# led_board_robot_vs_v2_final.net
KiCad netlist of a schematic drawn in EAGLE
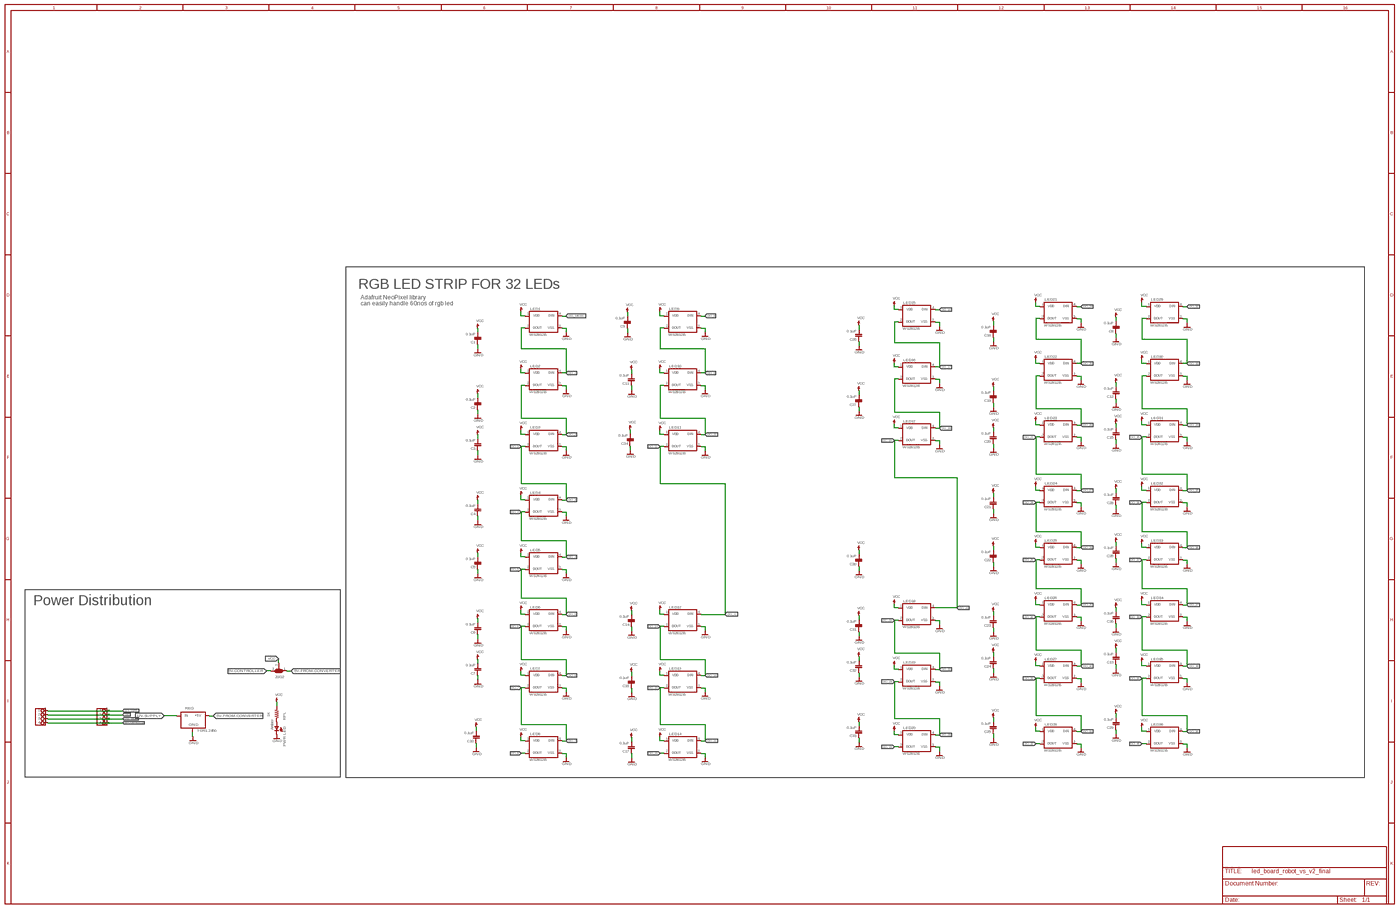
[diagram p0: schematic, sheet 1, overview]
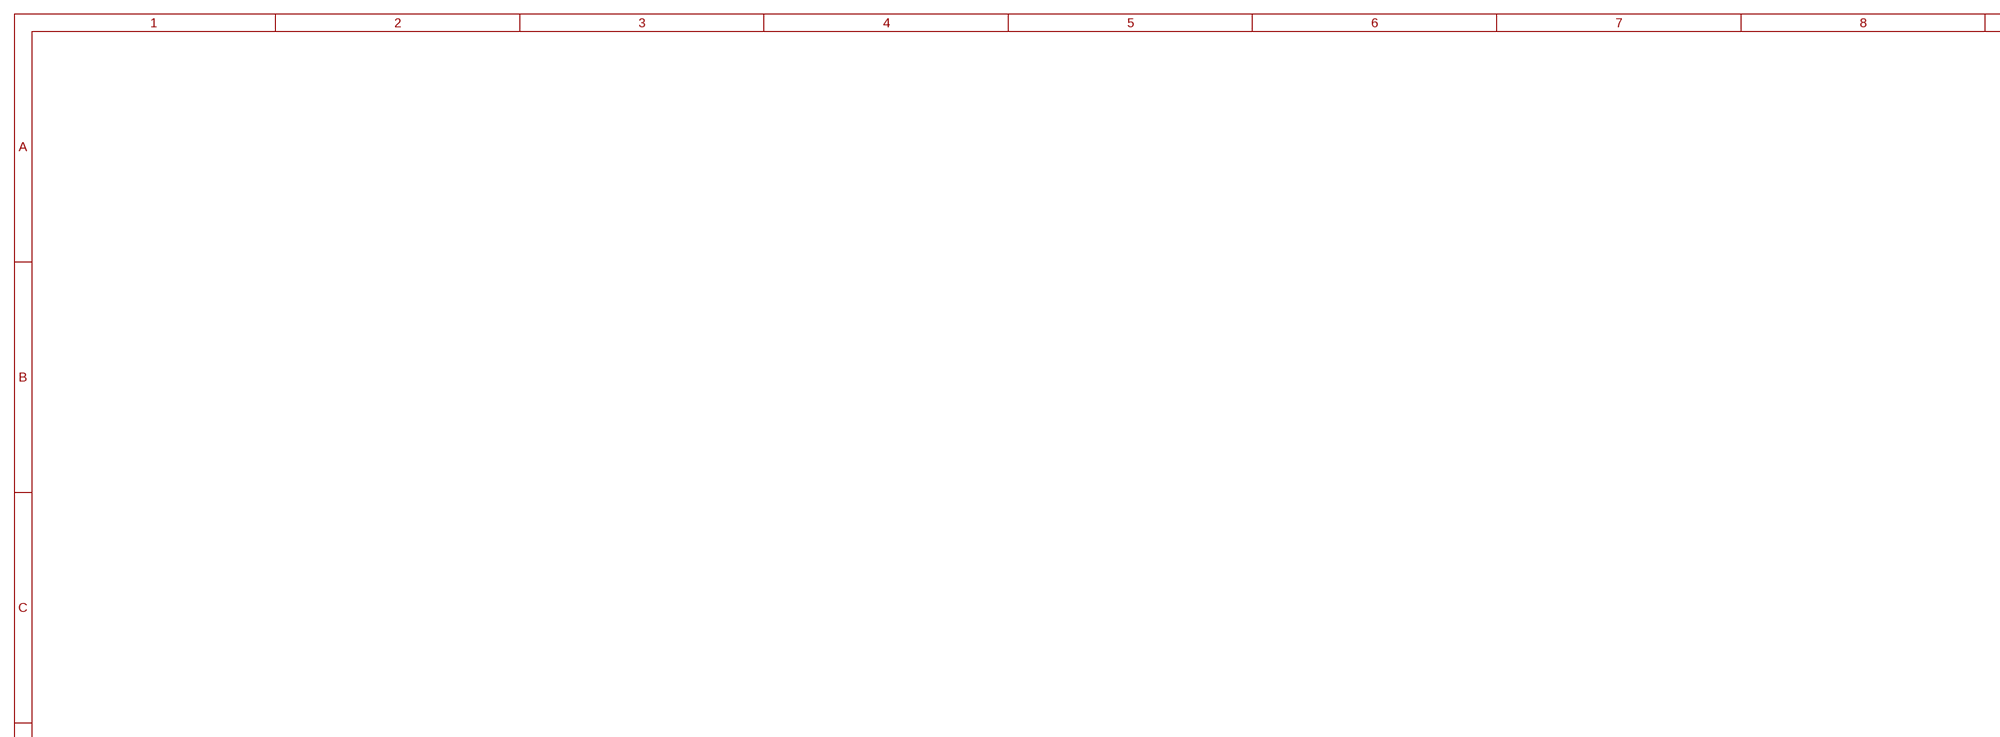
[diagram p1: schematic, sheet 1, part 1 of 4]
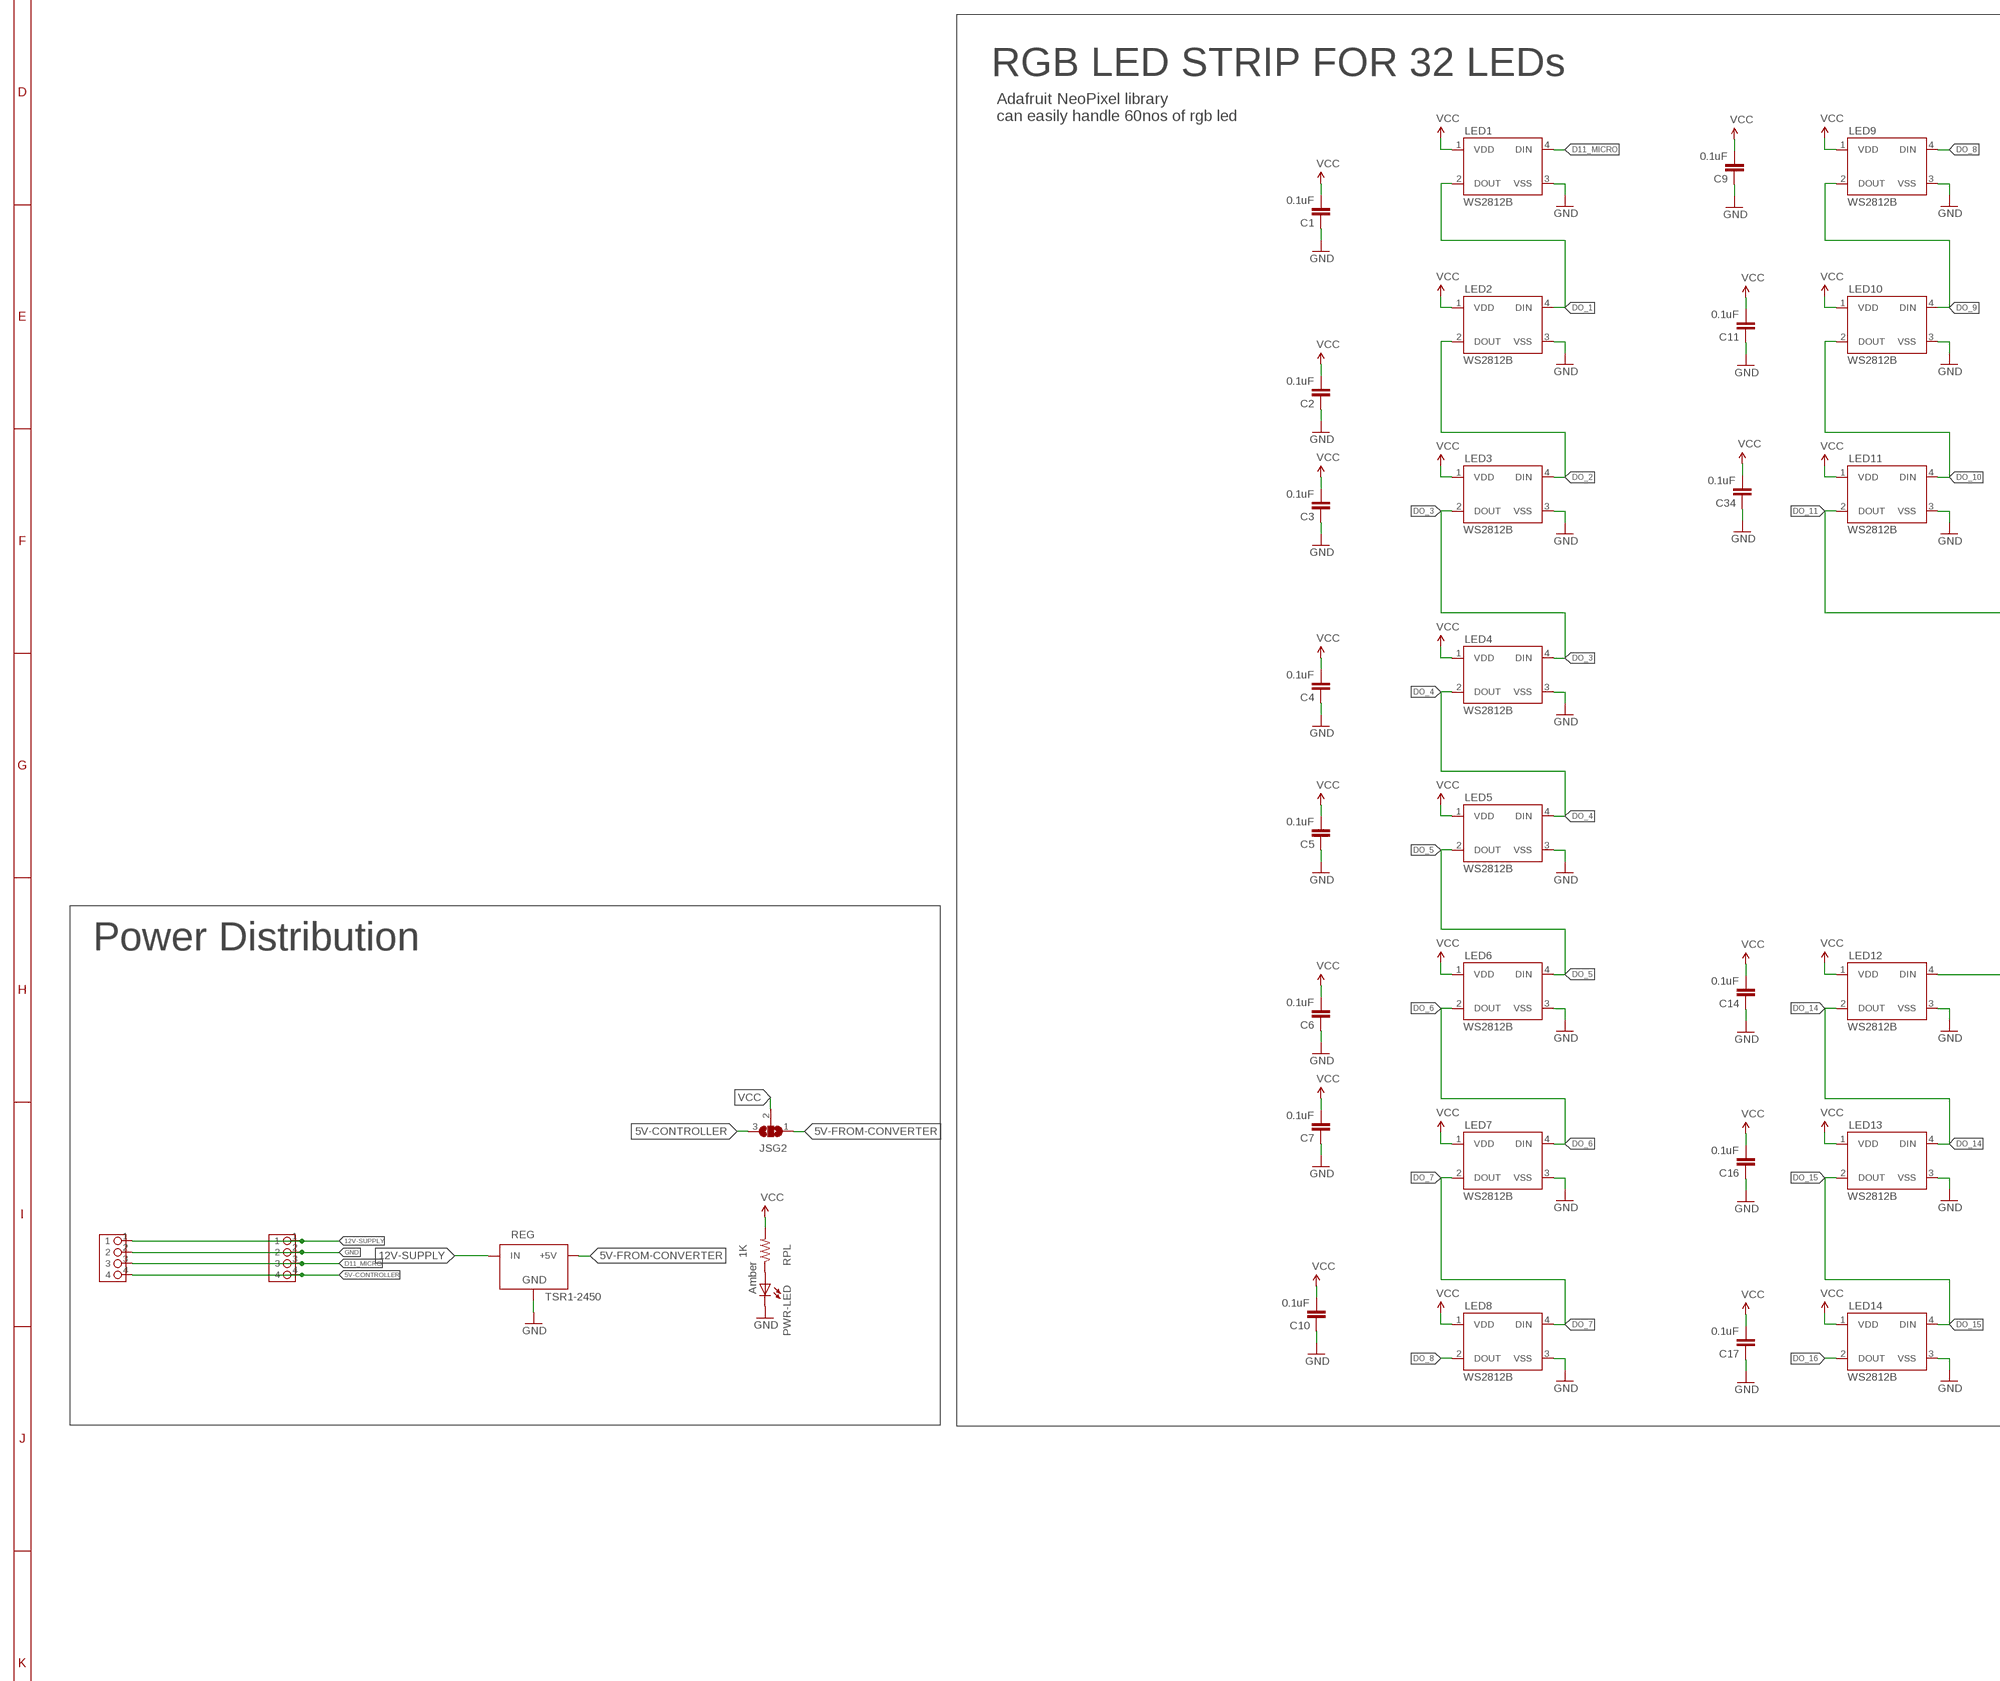
[diagram p2: schematic, sheet 1, part 2 of 4]
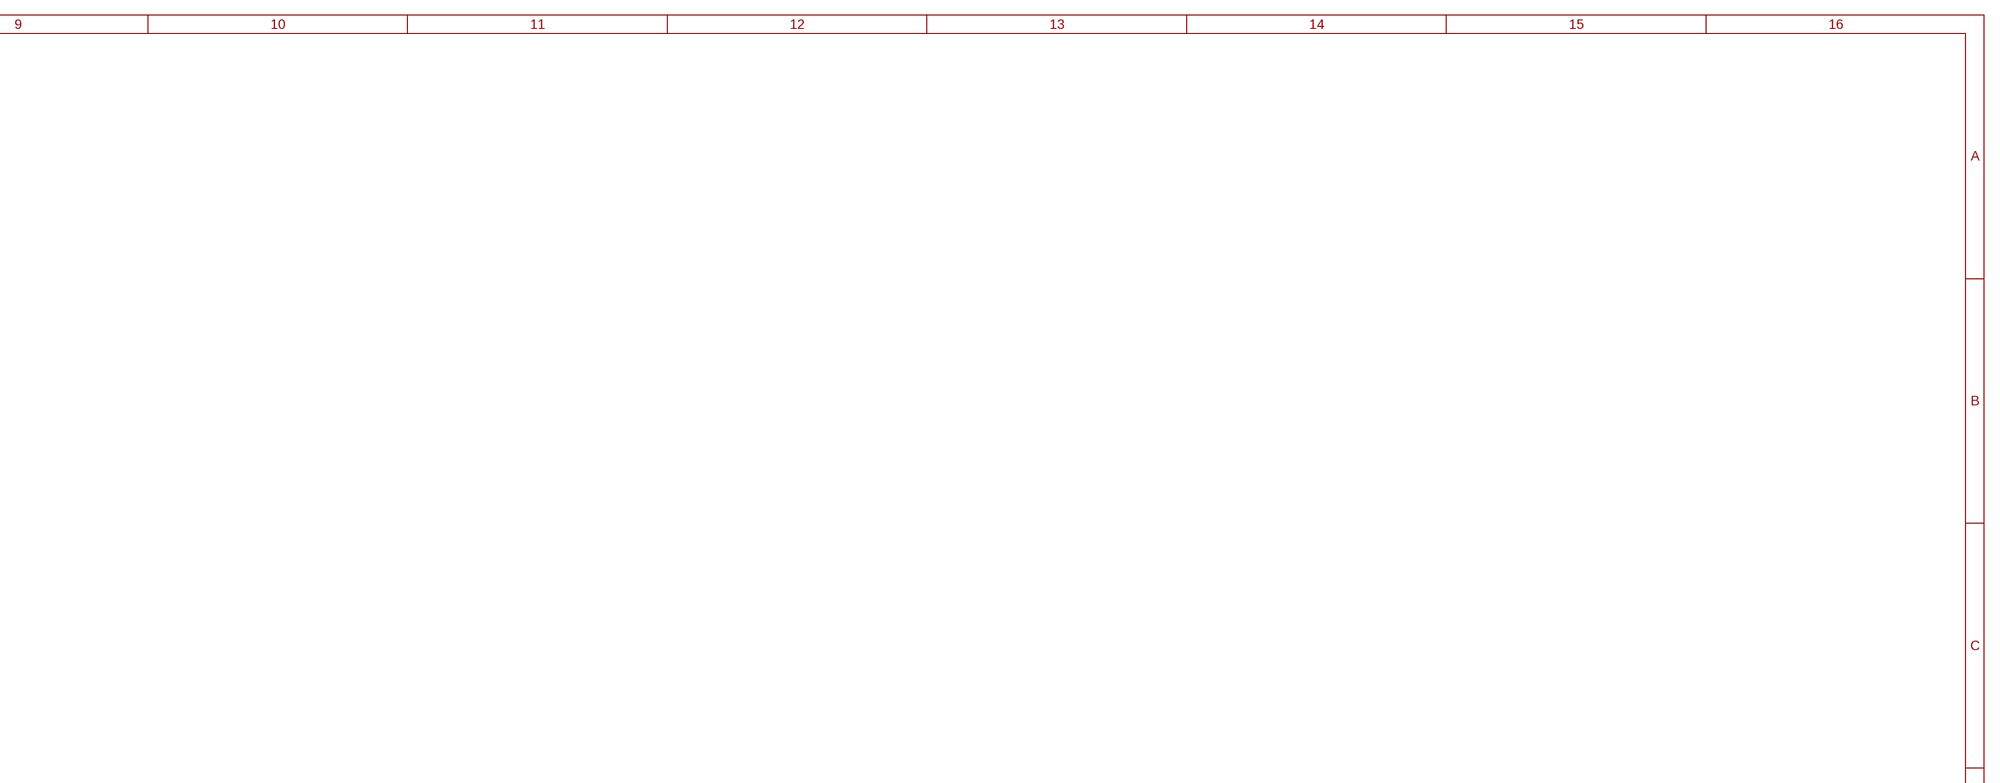
[diagram p3: schematic, sheet 1, part 3 of 4]
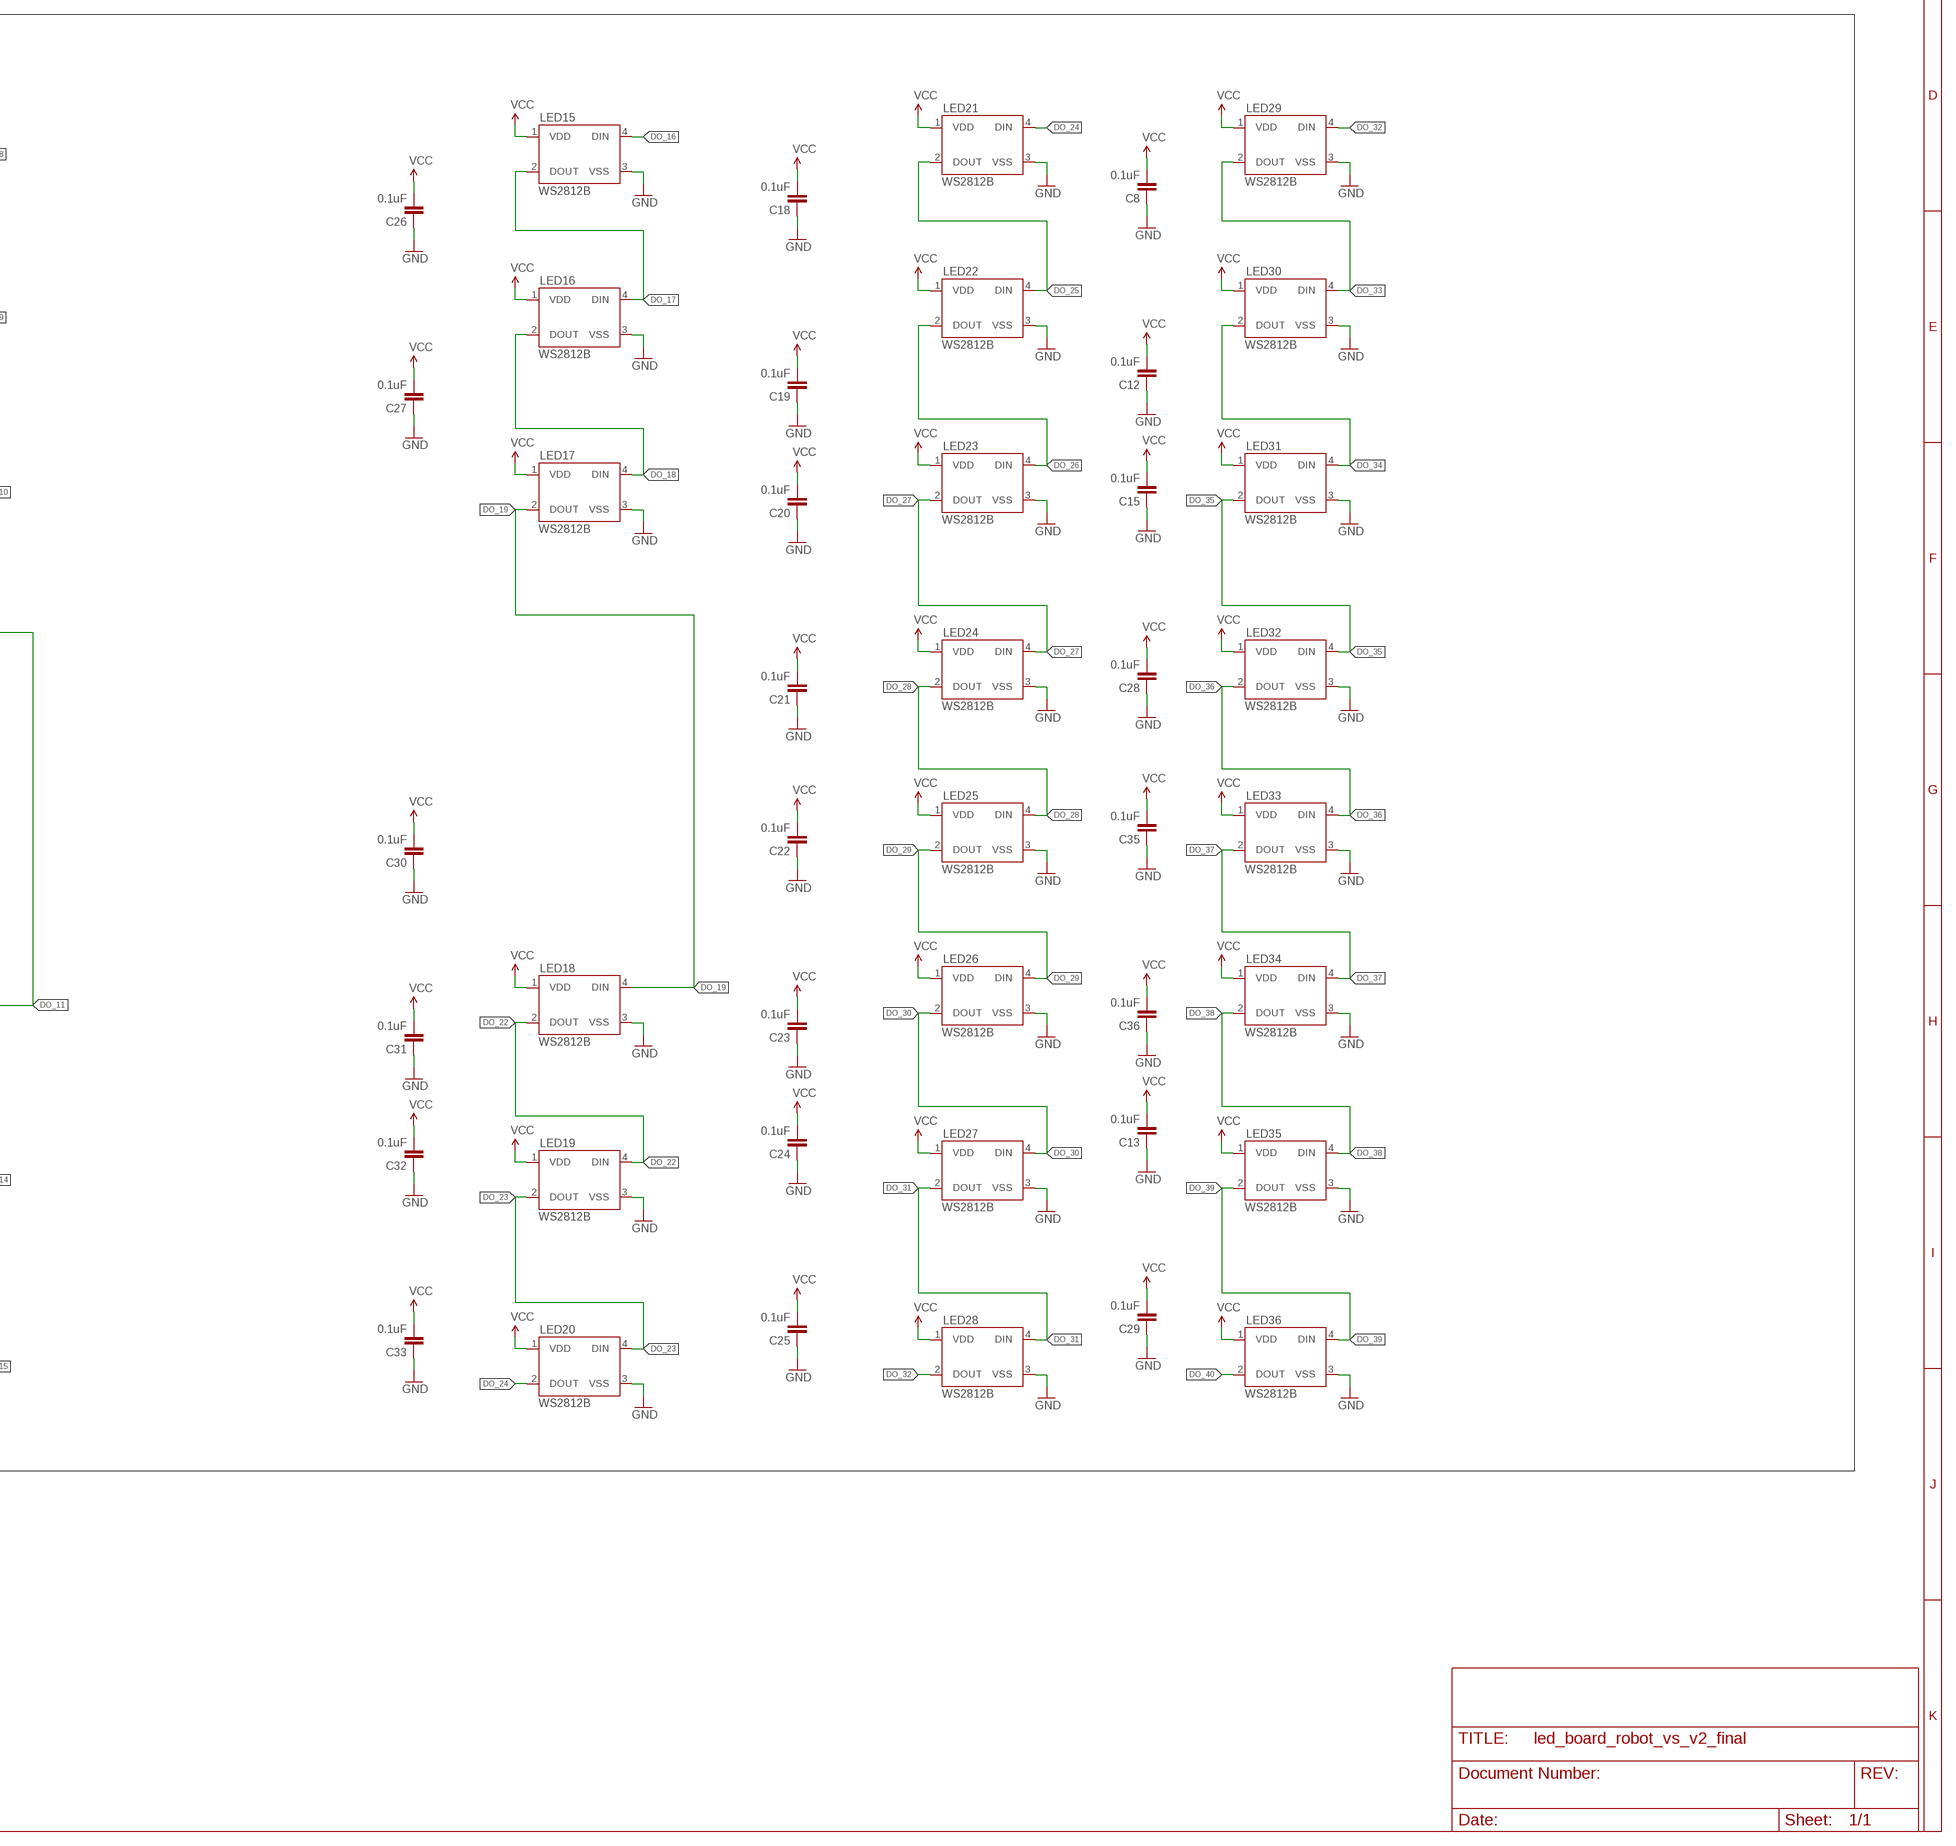
[diagram p4: schematic, sheet 1, part 4 of 4]

(export (version "E")
  (design (tool "Eeschema 10.0.6"))
  (components
    (comp (ref "C1")
      (value "0.1uF")
      (footprint "eagle-import:0603-CAP")
      (libsource (lib "eagle-import") (part "CAP0603-CAP"))
    )
    (comp (ref "C2")
      (value "0.1uF")
      (footprint "eagle-import:0603-CAP")
      (libsource (lib "eagle-import") (part "CAP0603-CAP"))
    )
    (comp (ref "C3")
      (value "0.1uF")
      (footprint "eagle-import:0603-CAP")
      (libsource (lib "eagle-import") (part "CAP0603-CAP"))
    )
    (comp (ref "C4")
      (value "0.1uF")
      (footprint "eagle-import:0603-CAP")
      (libsource (lib "eagle-import") (part "CAP0603-CAP"))
    )
    (comp (ref "C5")
      (value "0.1uF")
      (footprint "eagle-import:0603-CAP")
      (libsource (lib "eagle-import") (part "CAP0603-CAP"))
    )
    (comp (ref "C6")
      (value "0.1uF")
      (footprint "eagle-import:0603-CAP")
      (libsource (lib "eagle-import") (part "CAP0603-CAP"))
    )
    (comp (ref "C7")
      (value "0.1uF")
      (footprint "eagle-import:0603-CAP")
      (libsource (lib "eagle-import") (part "CAP0603-CAP"))
    )
    (comp (ref "C8")
      (value "0.1uF")
      (footprint "eagle-import:0603-CAP")
      (libsource (lib "eagle-import") (part "CAP0603-CAP"))
    )
    (comp (ref "C9")
      (value "0.1uF")
      (footprint "eagle-import:0603-CAP")
      (libsource (lib "eagle-import") (part "CAP0603-CAP"))
    )
    (comp (ref "C10")
      (value "0.1uF")
      (footprint "eagle-import:0603-CAP")
      (libsource (lib "eagle-import") (part "CAP0603-CAP"))
    )
    (comp (ref "C11")
      (value "0.1uF")
      (footprint "eagle-import:0603-CAP")
      (libsource (lib "eagle-import") (part "CAP0603-CAP"))
    )
    (comp (ref "C12")
      (value "0.1uF")
      (footprint "eagle-import:0603-CAP")
      (libsource (lib "eagle-import") (part "CAP0603-CAP"))
    )
    (comp (ref "C13")
      (value "0.1uF")
      (footprint "eagle-import:0603-CAP")
      (libsource (lib "eagle-import") (part "CAP0603-CAP"))
    )
    (comp (ref "C14")
      (value "0.1uF")
      (footprint "eagle-import:0603-CAP")
      (libsource (lib "eagle-import") (part "CAP0603-CAP"))
    )
    (comp (ref "C15")
      (value "0.1uF")
      (footprint "eagle-import:0603-CAP")
      (libsource (lib "eagle-import") (part "CAP0603-CAP"))
    )
    (comp (ref "C16")
      (value "0.1uF")
      (footprint "eagle-import:0603-CAP")
      (libsource (lib "eagle-import") (part "CAP0603-CAP"))
    )
    (comp (ref "C17")
      (value "0.1uF")
      (footprint "eagle-import:0603-CAP")
      (libsource (lib "eagle-import") (part "CAP0603-CAP"))
    )
    (comp (ref "C18")
      (value "0.1uF")
      (footprint "eagle-import:0603-CAP")
      (libsource (lib "eagle-import") (part "CAP0603-CAP"))
    )
    (comp (ref "C19")
      (value "0.1uF")
      (footprint "eagle-import:0603-CAP")
      (libsource (lib "eagle-import") (part "CAP0603-CAP"))
    )
    (comp (ref "C20")
      (value "0.1uF")
      (footprint "eagle-import:0603-CAP")
      (libsource (lib "eagle-import") (part "CAP0603-CAP"))
    )
    (comp (ref "C21")
      (value "0.1uF")
      (footprint "eagle-import:0603-CAP")
      (libsource (lib "eagle-import") (part "CAP0603-CAP"))
    )
    (comp (ref "C22")
      (value "0.1uF")
      (footprint "eagle-import:0603-CAP")
      (libsource (lib "eagle-import") (part "CAP0603-CAP"))
    )
    (comp (ref "C23")
      (value "0.1uF")
      (footprint "eagle-import:0603-CAP")
      (libsource (lib "eagle-import") (part "CAP0603-CAP"))
    )
    (comp (ref "C24")
      (value "0.1uF")
      (footprint "eagle-import:0603-CAP")
      (libsource (lib "eagle-import") (part "CAP0603-CAP"))
    )
    (comp (ref "C25")
      (value "0.1uF")
      (footprint "eagle-import:0603-CAP")
      (libsource (lib "eagle-import") (part "CAP0603-CAP"))
    )
    (comp (ref "C26")
      (value "0.1uF")
      (footprint "eagle-import:0603-CAP")
      (libsource (lib "eagle-import") (part "CAP0603-CAP"))
    )
    (comp (ref "C27")
      (value "0.1uF")
      (footprint "eagle-import:0603-CAP")
      (libsource (lib "eagle-import") (part "CAP0603-CAP"))
    )
    (comp (ref "C28")
      (value "0.1uF")
      (footprint "eagle-import:0603-CAP")
      (libsource (lib "eagle-import") (part "CAP0603-CAP"))
    )
    (comp (ref "C29")
      (value "0.1uF")
      (footprint "eagle-import:0603-CAP")
      (libsource (lib "eagle-import") (part "CAP0603-CAP"))
    )
    (comp (ref "C30")
      (value "0.1uF")
      (footprint "eagle-import:0603-CAP")
      (libsource (lib "eagle-import") (part "CAP0603-CAP"))
    )
    (comp (ref "C31")
      (value "0.1uF")
      (footprint "eagle-import:0603-CAP")
      (libsource (lib "eagle-import") (part "CAP0603-CAP"))
    )
    (comp (ref "C32")
      (value "0.1uF")
      (footprint "eagle-import:0603-CAP")
      (libsource (lib "eagle-import") (part "CAP0603-CAP"))
    )
    (comp (ref "C33")
      (value "0.1uF")
      (footprint "eagle-import:0603-CAP")
      (libsource (lib "eagle-import") (part "CAP0603-CAP"))
    )
    (comp (ref "C34")
      (value "0.1uF")
      (footprint "eagle-import:0603-CAP")
      (libsource (lib "eagle-import") (part "CAP0603-CAP"))
    )
    (comp (ref "C35")
      (value "0.1uF")
      (footprint "eagle-import:0603-CAP")
      (libsource (lib "eagle-import") (part "CAP0603-CAP"))
    )
    (comp (ref "C36")
      (value "0.1uF")
      (footprint "eagle-import:0603-CAP")
      (libsource (lib "eagle-import") (part "CAP0603-CAP"))
    )
    (comp (ref "CON1")
      (value "MOLEX_LOCKING_4PIN")
      (footprint "eagle-import:MOLEX_LOCKING_4PIN")
      (fields (field (name "PARTNO") "43650-0415"))
      (libsource (lib "eagle-import") (part "MOLEX_LOCKING_4PIN"))
    )
    (comp (ref "CON2")
      (value "MOLEX_LOCKING_4PIN")
      (footprint "eagle-import:MOLEX_LOCKING_4PIN")
      (fields (field (name "PARTNO") "43650-0415"))
      (libsource (lib "eagle-import") (part "MOLEX_LOCKING_4PIN"))
    )
    (comp (ref "JSG2")
      (value "SJ2WW")
      (footprint "eagle-import:SJ_2W")
      (libsource (lib "eagle-import") (part "SJ2WW"))
    )
    (comp (ref "LED1")
      (value "WS2812B")
      (footprint "eagle-import:WS2812B")
      (libsource (lib "eagle-import") (part "WS2812B"))
    )
    (comp (ref "LED2")
      (value "WS2812B")
      (footprint "eagle-import:WS2812B")
      (libsource (lib "eagle-import") (part "WS2812B"))
    )
    (comp (ref "LED3")
      (value "WS2812B")
      (footprint "eagle-import:WS2812B")
      (libsource (lib "eagle-import") (part "WS2812B"))
    )
    (comp (ref "LED4")
      (value "WS2812B")
      (footprint "eagle-import:WS2812B")
      (libsource (lib "eagle-import") (part "WS2812B"))
    )
    (comp (ref "LED5")
      (value "WS2812B")
      (footprint "eagle-import:WS2812B")
      (libsource (lib "eagle-import") (part "WS2812B"))
    )
    (comp (ref "LED6")
      (value "WS2812B")
      (footprint "eagle-import:WS2812B")
      (libsource (lib "eagle-import") (part "WS2812B"))
    )
    (comp (ref "LED7")
      (value "WS2812B")
      (footprint "eagle-import:WS2812B")
      (libsource (lib "eagle-import") (part "WS2812B"))
    )
    (comp (ref "LED8")
      (value "WS2812B")
      (footprint "eagle-import:WS2812B")
      (libsource (lib "eagle-import") (part "WS2812B"))
    )
    (comp (ref "LED9")
      (value "WS2812B")
      (footprint "eagle-import:WS2812B")
      (libsource (lib "eagle-import") (part "WS2812B"))
    )
    (comp (ref "LED10")
      (value "WS2812B")
      (footprint "eagle-import:WS2812B")
      (libsource (lib "eagle-import") (part "WS2812B"))
    )
    (comp (ref "LED11")
      (value "WS2812B")
      (footprint "eagle-import:WS2812B")
      (libsource (lib "eagle-import") (part "WS2812B"))
    )
    (comp (ref "LED12")
      (value "WS2812B")
      (footprint "eagle-import:WS2812B")
      (libsource (lib "eagle-import") (part "WS2812B"))
    )
    (comp (ref "LED13")
      (value "WS2812B")
      (footprint "eagle-import:WS2812B")
      (libsource (lib "eagle-import") (part "WS2812B"))
    )
    (comp (ref "LED14")
      (value "WS2812B")
      (footprint "eagle-import:WS2812B")
      (libsource (lib "eagle-import") (part "WS2812B"))
    )
    (comp (ref "LED15")
      (value "WS2812B")
      (footprint "eagle-import:WS2812B")
      (libsource (lib "eagle-import") (part "WS2812B"))
    )
    (comp (ref "LED16")
      (value "WS2812B")
      (footprint "eagle-import:WS2812B")
      (libsource (lib "eagle-import") (part "WS2812B"))
    )
    (comp (ref "LED17")
      (value "WS2812B")
      (footprint "eagle-import:WS2812B")
      (libsource (lib "eagle-import") (part "WS2812B"))
    )
    (comp (ref "LED18")
      (value "WS2812B")
      (footprint "eagle-import:WS2812B")
      (libsource (lib "eagle-import") (part "WS2812B"))
    )
    (comp (ref "LED19")
      (value "WS2812B")
      (footprint "eagle-import:WS2812B")
      (libsource (lib "eagle-import") (part "WS2812B"))
    )
    (comp (ref "LED20")
      (value "WS2812B")
      (footprint "eagle-import:WS2812B")
      (libsource (lib "eagle-import") (part "WS2812B"))
    )
    (comp (ref "LED21")
      (value "WS2812B")
      (footprint "eagle-import:WS2812B")
      (libsource (lib "eagle-import") (part "WS2812B"))
    )
    (comp (ref "LED22")
      (value "WS2812B")
      (footprint "eagle-import:WS2812B")
      (libsource (lib "eagle-import") (part "WS2812B"))
    )
    (comp (ref "LED23")
      (value "WS2812B")
      (footprint "eagle-import:WS2812B")
      (libsource (lib "eagle-import") (part "WS2812B"))
    )
    (comp (ref "LED24")
      (value "WS2812B")
      (footprint "eagle-import:WS2812B")
      (libsource (lib "eagle-import") (part "WS2812B"))
    )
    (comp (ref "LED25")
      (value "WS2812B")
      (footprint "eagle-import:WS2812B")
      (libsource (lib "eagle-import") (part "WS2812B"))
    )
    (comp (ref "LED26")
      (value "WS2812B")
      (footprint "eagle-import:WS2812B")
      (libsource (lib "eagle-import") (part "WS2812B"))
    )
    (comp (ref "LED27")
      (value "WS2812B")
      (footprint "eagle-import:WS2812B")
      (libsource (lib "eagle-import") (part "WS2812B"))
    )
    (comp (ref "LED28")
      (value "WS2812B")
      (footprint "eagle-import:WS2812B")
      (libsource (lib "eagle-import") (part "WS2812B"))
    )
    (comp (ref "LED29")
      (value "WS2812B")
      (footprint "eagle-import:WS2812B")
      (libsource (lib "eagle-import") (part "WS2812B"))
    )
    (comp (ref "LED30")
      (value "WS2812B")
      (footprint "eagle-import:WS2812B")
      (libsource (lib "eagle-import") (part "WS2812B"))
    )
    (comp (ref "LED31")
      (value "WS2812B")
      (footprint "eagle-import:WS2812B")
      (libsource (lib "eagle-import") (part "WS2812B"))
    )
    (comp (ref "LED32")
      (value "WS2812B")
      (footprint "eagle-import:WS2812B")
      (libsource (lib "eagle-import") (part "WS2812B"))
    )
    (comp (ref "LED33")
      (value "WS2812B")
      (footprint "eagle-import:WS2812B")
      (libsource (lib "eagle-import") (part "WS2812B"))
    )
    (comp (ref "LED34")
      (value "WS2812B")
      (footprint "eagle-import:WS2812B")
      (libsource (lib "eagle-import") (part "WS2812B"))
    )
    (comp (ref "LED35")
      (value "WS2812B")
      (footprint "eagle-import:WS2812B")
      (libsource (lib "eagle-import") (part "WS2812B"))
    )
    (comp (ref "LED36")
      (value "WS2812B")
      (footprint "eagle-import:WS2812B")
      (libsource (lib "eagle-import") (part "WS2812B"))
    )
    (comp (ref "PWR-LED")
      (value "Amber")
      (footprint "eagle-import:LED-0603")
      (libsource (lib "eagle-import") (part "LED0603"))
    )
    (comp (ref "REG")
      (value "TSR1-2450")
      (footprint "eagle-import:TSR-1")
      (libsource (lib "eagle-import") (part "TSR1-2450"))
    )
    (comp (ref "RPL")
      (value "1K")
      (footprint "eagle-import:0603-RES")
      (libsource (lib "eagle-import") (part "RESISTOR0603-RES"))
    )
  )
  (nets
    (net (code "1") (name "5V-CONTROLLER") (class "Default")
      (node (ref "CON1") (pin "4") (pinfunction "4_4") (pintype "bidirectional"))
      (node (ref "CON2") (pin "4") (pinfunction "4_4") (pintype "bidirectional"))
      (node (ref "JSG2") (pin "3") (pinfunction "3_3") (pintype "passive"))
    )
    (net (code "2") (name "5V-FROM-CONVERTER") (class "Default")
      (node (ref "JSG2") (pin "1") (pinfunction "1_1") (pintype "passive"))
      (node (ref "REG") (pin "3") (pinfunction "+5V_3") (pintype "power_in"))
    )
    (net (code "3") (name "12V-SUPPLY") (class "Default")
      (node (ref "CON1") (pin "1") (pinfunction "1_1") (pintype "bidirectional"))
      (node (ref "CON2") (pin "1") (pinfunction "1_1") (pintype "bidirectional"))
      (node (ref "REG") (pin "1") (pinfunction "IN_1") (pintype "power_in"))
    )
    (net (code "4") (name "D11_MICRO") (class "Default")
      (node (ref "CON1") (pin "3") (pinfunction "3_3") (pintype "bidirectional"))
      (node (ref "CON2") (pin "3") (pinfunction "3_3") (pintype "bidirectional"))
      (node (ref "LED1") (pin "4") (pinfunction "DIN_4") (pintype "input"))
    )
    (net (code "5") (name "DO_1") (class "Default")
      (node (ref "LED1") (pin "2") (pinfunction "DOUT_2") (pintype "output"))
      (node (ref "LED2") (pin "4") (pinfunction "DIN_4") (pintype "input"))
    )
    (net (code "6") (name "DO_2") (class "Default")
      (node (ref "LED2") (pin "2") (pinfunction "DOUT_2") (pintype "output"))
      (node (ref "LED3") (pin "4") (pinfunction "DIN_4") (pintype "input"))
    )
    (net (code "7") (name "DO_3") (class "Default")
      (node (ref "LED3") (pin "2") (pinfunction "DOUT_2") (pintype "output"))
      (node (ref "LED4") (pin "4") (pinfunction "DIN_4") (pintype "input"))
    )
    (net (code "8") (name "DO_4") (class "Default")
      (node (ref "LED4") (pin "2") (pinfunction "DOUT_2") (pintype "output"))
      (node (ref "LED5") (pin "4") (pinfunction "DIN_4") (pintype "input"))
    )
    (net (code "9") (name "DO_5") (class "Default")
      (node (ref "LED5") (pin "2") (pinfunction "DOUT_2") (pintype "output"))
      (node (ref "LED6") (pin "4") (pinfunction "DIN_4") (pintype "input"))
    )
    (net (code "10") (name "DO_6") (class "Default")
      (node (ref "LED6") (pin "2") (pinfunction "DOUT_2") (pintype "output"))
      (node (ref "LED7") (pin "4") (pinfunction "DIN_4") (pintype "input"))
    )
    (net (code "11") (name "DO_7") (class "Default")
      (node (ref "LED7") (pin "2") (pinfunction "DOUT_2") (pintype "output"))
      (node (ref "LED8") (pin "4") (pinfunction "DIN_4") (pintype "input"))
    )
    (net (code "12") (name "DO_8") (class "Default")
      (node (ref "LED8") (pin "2") (pinfunction "DOUT_2") (pintype "output"))
      (node (ref "LED9") (pin "4") (pinfunction "DIN_4") (pintype "input"))
    )
    (net (code "13") (name "DO_9") (class "Default")
      (node (ref "LED10") (pin "4") (pinfunction "DIN_4") (pintype "input"))
      (node (ref "LED9") (pin "2") (pinfunction "DOUT_2") (pintype "output"))
    )
    (net (code "14") (name "DO_10") (class "Default")
      (node (ref "LED10") (pin "2") (pinfunction "DOUT_2") (pintype "output"))
      (node (ref "LED11") (pin "4") (pinfunction "DIN_4") (pintype "input"))
    )
    (net (code "15") (name "DO_11") (class "Default")
      (node (ref "LED11") (pin "2") (pinfunction "DOUT_2") (pintype "output"))
      (node (ref "LED12") (pin "4") (pinfunction "DIN_4") (pintype "input"))
    )
    (net (code "16") (name "DO_14") (class "Default")
      (node (ref "LED12") (pin "2") (pinfunction "DOUT_2") (pintype "output"))
      (node (ref "LED13") (pin "4") (pinfunction "DIN_4") (pintype "input"))
    )
    (net (code "17") (name "DO_15") (class "Default")
      (node (ref "LED13") (pin "2") (pinfunction "DOUT_2") (pintype "output"))
      (node (ref "LED14") (pin "4") (pinfunction "DIN_4") (pintype "input"))
    )
    (net (code "18") (name "DO_16") (class "Default")
      (node (ref "LED14") (pin "2") (pinfunction "DOUT_2") (pintype "output"))
      (node (ref "LED15") (pin "4") (pinfunction "DIN_4") (pintype "input"))
    )
    (net (code "19") (name "DO_17") (class "Default")
      (node (ref "LED15") (pin "2") (pinfunction "DOUT_2") (pintype "output"))
      (node (ref "LED16") (pin "4") (pinfunction "DIN_4") (pintype "input"))
    )
    (net (code "20") (name "DO_18") (class "Default")
      (node (ref "LED16") (pin "2") (pinfunction "DOUT_2") (pintype "output"))
      (node (ref "LED17") (pin "4") (pinfunction "DIN_4") (pintype "input"))
    )
    (net (code "21") (name "DO_19") (class "Default")
      (node (ref "LED17") (pin "2") (pinfunction "DOUT_2") (pintype "output"))
      (node (ref "LED18") (pin "4") (pinfunction "DIN_4") (pintype "input"))
    )
    (net (code "22") (name "DO_22") (class "Default")
      (node (ref "LED18") (pin "2") (pinfunction "DOUT_2") (pintype "output"))
      (node (ref "LED19") (pin "4") (pinfunction "DIN_4") (pintype "input"))
    )
    (net (code "23") (name "DO_23") (class "Default")
      (node (ref "LED19") (pin "2") (pinfunction "DOUT_2") (pintype "output"))
      (node (ref "LED20") (pin "4") (pinfunction "DIN_4") (pintype "input"))
    )
    (net (code "24") (name "DO_24") (class "Default")
      (node (ref "LED20") (pin "2") (pinfunction "DOUT_2") (pintype "output"))
      (node (ref "LED21") (pin "4") (pinfunction "DIN_4") (pintype "input"))
    )
    (net (code "25") (name "DO_25") (class "Default")
      (node (ref "LED21") (pin "2") (pinfunction "DOUT_2") (pintype "output"))
      (node (ref "LED22") (pin "4") (pinfunction "DIN_4") (pintype "input"))
    )
    (net (code "26") (name "DO_26") (class "Default")
      (node (ref "LED22") (pin "2") (pinfunction "DOUT_2") (pintype "output"))
      (node (ref "LED23") (pin "4") (pinfunction "DIN_4") (pintype "input"))
    )
    (net (code "27") (name "DO_27") (class "Default")
      (node (ref "LED23") (pin "2") (pinfunction "DOUT_2") (pintype "output"))
      (node (ref "LED24") (pin "4") (pinfunction "DIN_4") (pintype "input"))
    )
    (net (code "28") (name "DO_28") (class "Default")
      (node (ref "LED24") (pin "2") (pinfunction "DOUT_2") (pintype "output"))
      (node (ref "LED25") (pin "4") (pinfunction "DIN_4") (pintype "input"))
    )
    (net (code "29") (name "DO_29") (class "Default")
      (node (ref "LED25") (pin "2") (pinfunction "DOUT_2") (pintype "output"))
      (node (ref "LED26") (pin "4") (pinfunction "DIN_4") (pintype "input"))
    )
    (net (code "30") (name "DO_30") (class "Default")
      (node (ref "LED26") (pin "2") (pinfunction "DOUT_2") (pintype "output"))
      (node (ref "LED27") (pin "4") (pinfunction "DIN_4") (pintype "input"))
    )
    (net (code "31") (name "DO_31") (class "Default")
      (node (ref "LED27") (pin "2") (pinfunction "DOUT_2") (pintype "output"))
      (node (ref "LED28") (pin "4") (pinfunction "DIN_4") (pintype "input"))
    )
    (net (code "32") (name "DO_32") (class "Default")
      (node (ref "LED28") (pin "2") (pinfunction "DOUT_2") (pintype "output"))
      (node (ref "LED29") (pin "4") (pinfunction "DIN_4") (pintype "input"))
    )
    (net (code "33") (name "DO_33") (class "Default")
      (node (ref "LED29") (pin "2") (pinfunction "DOUT_2") (pintype "output"))
      (node (ref "LED30") (pin "4") (pinfunction "DIN_4") (pintype "input"))
    )
    (net (code "34") (name "DO_34") (class "Default")
      (node (ref "LED30") (pin "2") (pinfunction "DOUT_2") (pintype "output"))
      (node (ref "LED31") (pin "4") (pinfunction "DIN_4") (pintype "input"))
    )
    (net (code "35") (name "DO_35") (class "Default")
      (node (ref "LED31") (pin "2") (pinfunction "DOUT_2") (pintype "output"))
      (node (ref "LED32") (pin "4") (pinfunction "DIN_4") (pintype "input"))
    )
    (net (code "36") (name "DO_36") (class "Default")
      (node (ref "LED32") (pin "2") (pinfunction "DOUT_2") (pintype "output"))
      (node (ref "LED33") (pin "4") (pinfunction "DIN_4") (pintype "input"))
    )
    (net (code "37") (name "DO_37") (class "Default")
      (node (ref "LED33") (pin "2") (pinfunction "DOUT_2") (pintype "output"))
      (node (ref "LED34") (pin "4") (pinfunction "DIN_4") (pintype "input"))
    )
    (net (code "38") (name "DO_38") (class "Default")
      (node (ref "LED34") (pin "2") (pinfunction "DOUT_2") (pintype "output"))
      (node (ref "LED35") (pin "4") (pinfunction "DIN_4") (pintype "input"))
    )
    (net (code "39") (name "DO_39") (class "Default")
      (node (ref "LED35") (pin "2") (pinfunction "DOUT_2") (pintype "output"))
      (node (ref "LED36") (pin "4") (pinfunction "DIN_4") (pintype "input"))
    )
    (net (code "40") (name "DO_40") (class "Default")
      (node (ref "LED36") (pin "2") (pinfunction "DOUT_2") (pintype "output"))
    )
    (net (code "41") (name "GND") (class "Default")
      (node (ref "C1") (pin "1") (pinfunction "1_1") (pintype "passive"))
      (node (ref "C10") (pin "1") (pinfunction "1_1") (pintype "passive"))
      (node (ref "C11") (pin "1") (pinfunction "1_1") (pintype "passive"))
      (node (ref "C12") (pin "1") (pinfunction "1_1") (pintype "passive"))
      (node (ref "C13") (pin "1") (pinfunction "1_1") (pintype "passive"))
      (node (ref "C14") (pin "1") (pinfunction "1_1") (pintype "passive"))
      (node (ref "C15") (pin "1") (pinfunction "1_1") (pintype "passive"))
      (node (ref "C16") (pin "1") (pinfunction "1_1") (pintype "passive"))
      (node (ref "C17") (pin "1") (pinfunction "1_1") (pintype "passive"))
      (node (ref "C18") (pin "1") (pinfunction "1_1") (pintype "passive"))
      (node (ref "C19") (pin "1") (pinfunction "1_1") (pintype "passive"))
      (node (ref "C2") (pin "1") (pinfunction "1_1") (pintype "passive"))
      (node (ref "C20") (pin "1") (pinfunction "1_1") (pintype "passive"))
      (node (ref "C21") (pin "1") (pinfunction "1_1") (pintype "passive"))
      (node (ref "C22") (pin "1") (pinfunction "1_1") (pintype "passive"))
      (node (ref "C23") (pin "1") (pinfunction "1_1") (pintype "passive"))
      (node (ref "C24") (pin "1") (pinfunction "1_1") (pintype "passive"))
      (node (ref "C25") (pin "1") (pinfunction "1_1") (pintype "passive"))
      (node (ref "C26") (pin "1") (pinfunction "1_1") (pintype "passive"))
      (node (ref "C27") (pin "1") (pinfunction "1_1") (pintype "passive"))
      (node (ref "C28") (pin "1") (pinfunction "1_1") (pintype "passive"))
      (node (ref "C29") (pin "1") (pinfunction "1_1") (pintype "passive"))
      (node (ref "C3") (pin "1") (pinfunction "1_1") (pintype "passive"))
      (node (ref "C30") (pin "1") (pinfunction "1_1") (pintype "passive"))
      (node (ref "C31") (pin "1") (pinfunction "1_1") (pintype "passive"))
      (node (ref "C32") (pin "1") (pinfunction "1_1") (pintype "passive"))
      (node (ref "C33") (pin "1") (pinfunction "1_1") (pintype "passive"))
      (node (ref "C34") (pin "1") (pinfunction "1_1") (pintype "passive"))
      (node (ref "C35") (pin "1") (pinfunction "1_1") (pintype "passive"))
      (node (ref "C36") (pin "1") (pinfunction "1_1") (pintype "passive"))
      (node (ref "C4") (pin "1") (pinfunction "1_1") (pintype "passive"))
      (node (ref "C5") (pin "1") (pinfunction "1_1") (pintype "passive"))
      (node (ref "C6") (pin "1") (pinfunction "1_1") (pintype "passive"))
      (node (ref "C7") (pin "1") (pinfunction "1_1") (pintype "passive"))
      (node (ref "C8") (pin "1") (pinfunction "1_1") (pintype "passive"))
      (node (ref "C9") (pin "1") (pinfunction "1_1") (pintype "passive"))
      (node (ref "CON1") (pin "2") (pinfunction "2_2") (pintype "bidirectional"))
      (node (ref "CON2") (pin "2") (pinfunction "2_2") (pintype "bidirectional"))
      (node (ref "LED1") (pin "3") (pinfunction "VSS_3") (pintype "power_in"))
      (node (ref "LED10") (pin "3") (pinfunction "VSS_3") (pintype "power_in"))
      (node (ref "LED11") (pin "3") (pinfunction "VSS_3") (pintype "power_in"))
      (node (ref "LED12") (pin "3") (pinfunction "VSS_3") (pintype "power_in"))
      (node (ref "LED13") (pin "3") (pinfunction "VSS_3") (pintype "power_in"))
      (node (ref "LED14") (pin "3") (pinfunction "VSS_3") (pintype "power_in"))
      (node (ref "LED15") (pin "3") (pinfunction "VSS_3") (pintype "power_in"))
      (node (ref "LED16") (pin "3") (pinfunction "VSS_3") (pintype "power_in"))
      (node (ref "LED17") (pin "3") (pinfunction "VSS_3") (pintype "power_in"))
      (node (ref "LED18") (pin "3") (pinfunction "VSS_3") (pintype "power_in"))
      (node (ref "LED19") (pin "3") (pinfunction "VSS_3") (pintype "power_in"))
      (node (ref "LED2") (pin "3") (pinfunction "VSS_3") (pintype "power_in"))
      (node (ref "LED20") (pin "3") (pinfunction "VSS_3") (pintype "power_in"))
      (node (ref "LED21") (pin "3") (pinfunction "VSS_3") (pintype "power_in"))
      (node (ref "LED22") (pin "3") (pinfunction "VSS_3") (pintype "power_in"))
      (node (ref "LED23") (pin "3") (pinfunction "VSS_3") (pintype "power_in"))
      (node (ref "LED24") (pin "3") (pinfunction "VSS_3") (pintype "power_in"))
      (node (ref "LED25") (pin "3") (pinfunction "VSS_3") (pintype "power_in"))
      (node (ref "LED26") (pin "3") (pinfunction "VSS_3") (pintype "power_in"))
      (node (ref "LED27") (pin "3") (pinfunction "VSS_3") (pintype "power_in"))
      (node (ref "LED28") (pin "3") (pinfunction "VSS_3") (pintype "power_in"))
      (node (ref "LED29") (pin "3") (pinfunction "VSS_3") (pintype "power_in"))
      (node (ref "LED3") (pin "3") (pinfunction "VSS_3") (pintype "power_in"))
      (node (ref "LED30") (pin "3") (pinfunction "VSS_3") (pintype "power_in"))
      (node (ref "LED31") (pin "3") (pinfunction "VSS_3") (pintype "power_in"))
      (node (ref "LED32") (pin "3") (pinfunction "VSS_3") (pintype "power_in"))
      (node (ref "LED33") (pin "3") (pinfunction "VSS_3") (pintype "power_in"))
      (node (ref "LED34") (pin "3") (pinfunction "VSS_3") (pintype "power_in"))
      (node (ref "LED35") (pin "3") (pinfunction "VSS_3") (pintype "power_in"))
      (node (ref "LED36") (pin "3") (pinfunction "VSS_3") (pintype "power_in"))
      (node (ref "LED4") (pin "3") (pinfunction "VSS_3") (pintype "power_in"))
      (node (ref "LED5") (pin "3") (pinfunction "VSS_3") (pintype "power_in"))
      (node (ref "LED6") (pin "3") (pinfunction "VSS_3") (pintype "power_in"))
      (node (ref "LED7") (pin "3") (pinfunction "VSS_3") (pintype "power_in"))
      (node (ref "LED8") (pin "3") (pinfunction "VSS_3") (pintype "power_in"))
      (node (ref "LED9") (pin "3") (pinfunction "VSS_3") (pintype "power_in"))
      (node (ref "PWR-LED") (pin "C") (pinfunction "C_C") (pintype "passive"))
      (node (ref "REG") (pin "2") (pinfunction "GND_2") (pintype "power_in"))
    )
    (net (code "42") (name "Net-(PWR-LED-PadA)") (class "Default")
      (node (ref "PWR-LED") (pin "A") (pinfunction "A_A") (pintype "passive"))
      (node (ref "RPL") (pin "1") (pinfunction "1_1") (pintype "passive"))
    )
    (net (code "43") (name "VCC") (class "Default")
      (node (ref "C1") (pin "2") (pinfunction "2_2") (pintype "passive"))
      (node (ref "C10") (pin "2") (pinfunction "2_2") (pintype "passive"))
      (node (ref "C11") (pin "2") (pinfunction "2_2") (pintype "passive"))
      (node (ref "C12") (pin "2") (pinfunction "2_2") (pintype "passive"))
      (node (ref "C13") (pin "2") (pinfunction "2_2") (pintype "passive"))
      (node (ref "C14") (pin "2") (pinfunction "2_2") (pintype "passive"))
      (node (ref "C15") (pin "2") (pinfunction "2_2") (pintype "passive"))
      (node (ref "C16") (pin "2") (pinfunction "2_2") (pintype "passive"))
      (node (ref "C17") (pin "2") (pinfunction "2_2") (pintype "passive"))
      (node (ref "C18") (pin "2") (pinfunction "2_2") (pintype "passive"))
      (node (ref "C19") (pin "2") (pinfunction "2_2") (pintype "passive"))
      (node (ref "C2") (pin "2") (pinfunction "2_2") (pintype "passive"))
      (node (ref "C20") (pin "2") (pinfunction "2_2") (pintype "passive"))
      (node (ref "C21") (pin "2") (pinfunction "2_2") (pintype "passive"))
      (node (ref "C22") (pin "2") (pinfunction "2_2") (pintype "passive"))
      (node (ref "C23") (pin "2") (pinfunction "2_2") (pintype "passive"))
      (node (ref "C24") (pin "2") (pinfunction "2_2") (pintype "passive"))
      (node (ref "C25") (pin "2") (pinfunction "2_2") (pintype "passive"))
      (node (ref "C26") (pin "2") (pinfunction "2_2") (pintype "passive"))
      (node (ref "C27") (pin "2") (pinfunction "2_2") (pintype "passive"))
      (node (ref "C28") (pin "2") (pinfunction "2_2") (pintype "passive"))
      (node (ref "C29") (pin "2") (pinfunction "2_2") (pintype "passive"))
      (node (ref "C3") (pin "2") (pinfunction "2_2") (pintype "passive"))
      (node (ref "C30") (pin "2") (pinfunction "2_2") (pintype "passive"))
      (node (ref "C31") (pin "2") (pinfunction "2_2") (pintype "passive"))
      (node (ref "C32") (pin "2") (pinfunction "2_2") (pintype "passive"))
      (node (ref "C33") (pin "2") (pinfunction "2_2") (pintype "passive"))
      (node (ref "C34") (pin "2") (pinfunction "2_2") (pintype "passive"))
      (node (ref "C35") (pin "2") (pinfunction "2_2") (pintype "passive"))
      (node (ref "C36") (pin "2") (pinfunction "2_2") (pintype "passive"))
      (node (ref "C4") (pin "2") (pinfunction "2_2") (pintype "passive"))
      (node (ref "C5") (pin "2") (pinfunction "2_2") (pintype "passive"))
      (node (ref "C6") (pin "2") (pinfunction "2_2") (pintype "passive"))
      (node (ref "C7") (pin "2") (pinfunction "2_2") (pintype "passive"))
      (node (ref "C8") (pin "2") (pinfunction "2_2") (pintype "passive"))
      (node (ref "C9") (pin "2") (pinfunction "2_2") (pintype "passive"))
      (node (ref "JSG2") (pin "2") (pinfunction "2_2") (pintype "passive"))
      (node (ref "LED1") (pin "1") (pinfunction "VDD_1") (pintype "power_in"))
      (node (ref "LED10") (pin "1") (pinfunction "VDD_1") (pintype "power_in"))
      (node (ref "LED11") (pin "1") (pinfunction "VDD_1") (pintype "power_in"))
      (node (ref "LED12") (pin "1") (pinfunction "VDD_1") (pintype "power_in"))
      (node (ref "LED13") (pin "1") (pinfunction "VDD_1") (pintype "power_in"))
      (node (ref "LED14") (pin "1") (pinfunction "VDD_1") (pintype "power_in"))
      (node (ref "LED15") (pin "1") (pinfunction "VDD_1") (pintype "power_in"))
      (node (ref "LED16") (pin "1") (pinfunction "VDD_1") (pintype "power_in"))
      (node (ref "LED17") (pin "1") (pinfunction "VDD_1") (pintype "power_in"))
      (node (ref "LED18") (pin "1") (pinfunction "VDD_1") (pintype "power_in"))
      (node (ref "LED19") (pin "1") (pinfunction "VDD_1") (pintype "power_in"))
      (node (ref "LED2") (pin "1") (pinfunction "VDD_1") (pintype "power_in"))
      (node (ref "LED20") (pin "1") (pinfunction "VDD_1") (pintype "power_in"))
      (node (ref "LED21") (pin "1") (pinfunction "VDD_1") (pintype "power_in"))
      (node (ref "LED22") (pin "1") (pinfunction "VDD_1") (pintype "power_in"))
      (node (ref "LED23") (pin "1") (pinfunction "VDD_1") (pintype "power_in"))
      (node (ref "LED24") (pin "1") (pinfunction "VDD_1") (pintype "power_in"))
      (node (ref "LED25") (pin "1") (pinfunction "VDD_1") (pintype "power_in"))
      (node (ref "LED26") (pin "1") (pinfunction "VDD_1") (pintype "power_in"))
      (node (ref "LED27") (pin "1") (pinfunction "VDD_1") (pintype "power_in"))
      (node (ref "LED28") (pin "1") (pinfunction "VDD_1") (pintype "power_in"))
      (node (ref "LED29") (pin "1") (pinfunction "VDD_1") (pintype "power_in"))
      (node (ref "LED3") (pin "1") (pinfunction "VDD_1") (pintype "power_in"))
      (node (ref "LED30") (pin "1") (pinfunction "VDD_1") (pintype "power_in"))
      (node (ref "LED31") (pin "1") (pinfunction "VDD_1") (pintype "power_in"))
      (node (ref "LED32") (pin "1") (pinfunction "VDD_1") (pintype "power_in"))
      (node (ref "LED33") (pin "1") (pinfunction "VDD_1") (pintype "power_in"))
      (node (ref "LED34") (pin "1") (pinfunction "VDD_1") (pintype "power_in"))
      (node (ref "LED35") (pin "1") (pinfunction "VDD_1") (pintype "power_in"))
      (node (ref "LED36") (pin "1") (pinfunction "VDD_1") (pintype "power_in"))
      (node (ref "LED4") (pin "1") (pinfunction "VDD_1") (pintype "power_in"))
      (node (ref "LED5") (pin "1") (pinfunction "VDD_1") (pintype "power_in"))
      (node (ref "LED6") (pin "1") (pinfunction "VDD_1") (pintype "power_in"))
      (node (ref "LED7") (pin "1") (pinfunction "VDD_1") (pintype "power_in"))
      (node (ref "LED8") (pin "1") (pinfunction "VDD_1") (pintype "power_in"))
      (node (ref "LED9") (pin "1") (pinfunction "VDD_1") (pintype "power_in"))
      (node (ref "RPL") (pin "2") (pinfunction "2_2") (pintype "passive"))
    )
  )
)
